# fonte-ajustavel.net
KiCad netlist of a schematic drawn in EAGLE
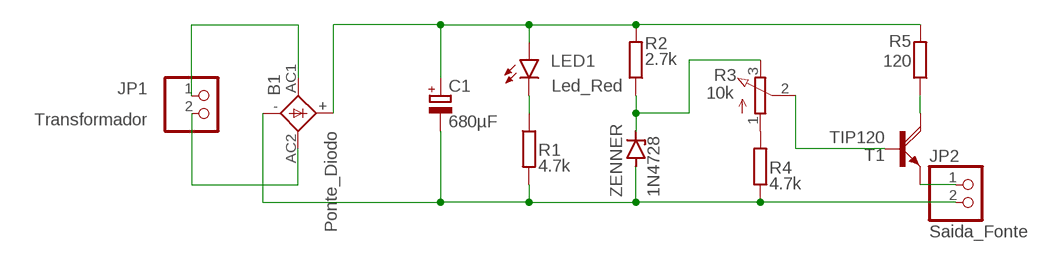
[diagram p0: schematic, sheet 1]

(export (version "E")
  (design (tool "Eeschema 10.0.6"))
  (components
    (comp (ref "B1")
      (value "Ponte_Diodo")
      (footprint "eagle-import:1KAB")
      (libsource (lib "eagle-import") (part "1KAB"))
    )
    (comp (ref "C1")
      (value "680µF")
      (footprint "eagle-import:E5-10,5")
      (libsource (lib "eagle-import") (part "CPOL-EUE5-10.5"))
    )
    (comp (ref "JP1")
      (value "Transformador")
      (footprint "eagle-import:1X02")
      (libsource (lib "eagle-import") (part "PINHD-1X2"))
    )
    (comp (ref "JP2")
      (value "Saida_Fonte")
      (footprint "eagle-import:1X02")
      (libsource (lib "eagle-import") (part "PINHD-1X2"))
    )
    (comp (ref "LED1")
      (value "Led_Red")
      (footprint "eagle-import:LED5MM")
      (libsource (lib "eagle-import") (part "LED5MM"))
    )
    (comp (ref "R1")
      (value "4.7k")
      (footprint "eagle-import:0204_7")
      (libsource (lib "eagle-import") (part "R-EU_0204/7"))
    )
    (comp (ref "R2")
      (value "2.7k")
      (footprint "eagle-import:0204_7")
      (libsource (lib "eagle-import") (part "R-EU_0204/7"))
    )
    (comp (ref "R3")
      (value "10k")
      (footprint "eagle-import:3RP_1610N")
      (libsource (lib "eagle-import") (part "3RP/1610N"))
    )
    (comp (ref "R4")
      (value "4.7k")
      (footprint "eagle-import:0204_7")
      (libsource (lib "eagle-import") (part "R-EU_0204/7"))
    )
    (comp (ref "R5")
      (value "120")
      (footprint "eagle-import:0204_7")
      (libsource (lib "eagle-import") (part "R-EU_0204/7"))
    )
    (comp (ref "T1")
      (value "TIP120")
      (footprint "eagle-import:TO220AH")
      (libsource (lib "eagle-import") (part "TIP120"))
    )
    (comp (ref "ZENNER")
      (value "1N4728")
      (footprint "eagle-import:DO41Z10")
      (libsource (lib "eagle-import") (part "1N4728"))
    )
  )
  (nets
    (net (code "1") (name "Net-(B1-Pad+)") (class "Default")
      (node (ref "B1") (pin "+") (pinfunction "+_+") (pintype "passive"))
      (node (ref "C1") (pin "+") (pinfunction "+_+") (pintype "passive"))
      (node (ref "LED1") (pin "A") (pinfunction "A_A") (pintype "passive"))
      (node (ref "R2") (pin "2") (pinfunction "2_2") (pintype "passive"))
      (node (ref "R5") (pin "2") (pinfunction "2_2") (pintype "passive"))
    )
    (net (code "2") (name "Net-(B1-Pad-)") (class "Default")
      (node (ref "B1") (pin "-") (pinfunction "-_-") (pintype "passive"))
      (node (ref "C1") (pin "-") (pinfunction "-_-") (pintype "passive"))
      (node (ref "JP2") (pin "2") (pinfunction "2_2") (pintype "passive"))
      (node (ref "R1") (pin "2") (pinfunction "2_2") (pintype "passive"))
      (node (ref "R4") (pin "1") (pinfunction "1_1") (pintype "passive"))
      (node (ref "ZENNER") (pin "A") (pinfunction "A_A") (pintype "passive"))
    )
    (net (code "3") (name "Net-(B1-PadAC1)") (class "Default")
      (node (ref "B1") (pin "AC1") (pinfunction "AC1_AC1") (pintype "passive"))
      (node (ref "JP1") (pin "1") (pinfunction "1_1") (pintype "passive"))
    )
    (net (code "4") (name "Net-(B1-PadAC2)") (class "Default")
      (node (ref "B1") (pin "AC2") (pinfunction "AC2_AC2") (pintype "passive"))
      (node (ref "JP1") (pin "2") (pinfunction "2_2") (pintype "passive"))
    )
    (net (code "5") (name "Net-(JP2-Pad1)") (class "Default")
      (node (ref "JP2") (pin "1") (pinfunction "1_1") (pintype "passive"))
      (node (ref "T1") (pin "E") (pinfunction "E_E") (pintype "passive"))
    )
    (net (code "6") (name "Net-(LED1-C)") (class "Default")
      (node (ref "LED1") (pin "K") (pinfunction "C_K") (pintype "passive"))
      (node (ref "R1") (pin "1") (pinfunction "1_1") (pintype "passive"))
    )
    (net (code "7") (name "Net-(R3-A)") (class "Default")
      (node (ref "R3") (pin "1") (pinfunction "A_1") (pintype "passive"))
      (node (ref "R4") (pin "2") (pinfunction "2_2") (pintype "passive"))
    )
    (net (code "8") (name "Net-(R3-E)") (class "Default")
      (node (ref "R2") (pin "1") (pinfunction "1_1") (pintype "passive"))
      (node (ref "R3") (pin "3") (pinfunction "E_3") (pintype "passive"))
      (node (ref "ZENNER") (pin "C") (pinfunction "C_C") (pintype "passive"))
    )
    (net (code "9") (name "Net-(R3-S)") (class "Default")
      (node (ref "R3") (pin "2") (pinfunction "S_2") (pintype "passive"))
      (node (ref "T1") (pin "B") (pinfunction "B_B") (pintype "passive"))
    )
    (net (code "10") (name "Net-(R5-Pad1)") (class "Default")
      (node (ref "R5") (pin "1") (pinfunction "1_1") (pintype "passive"))
      (node (ref "T1") (pin "C") (pinfunction "C_C") (pintype "passive"))
    )
  )
)
